# scara_robot.net
KiCad netlist of a schematic drawn in EasyEDA
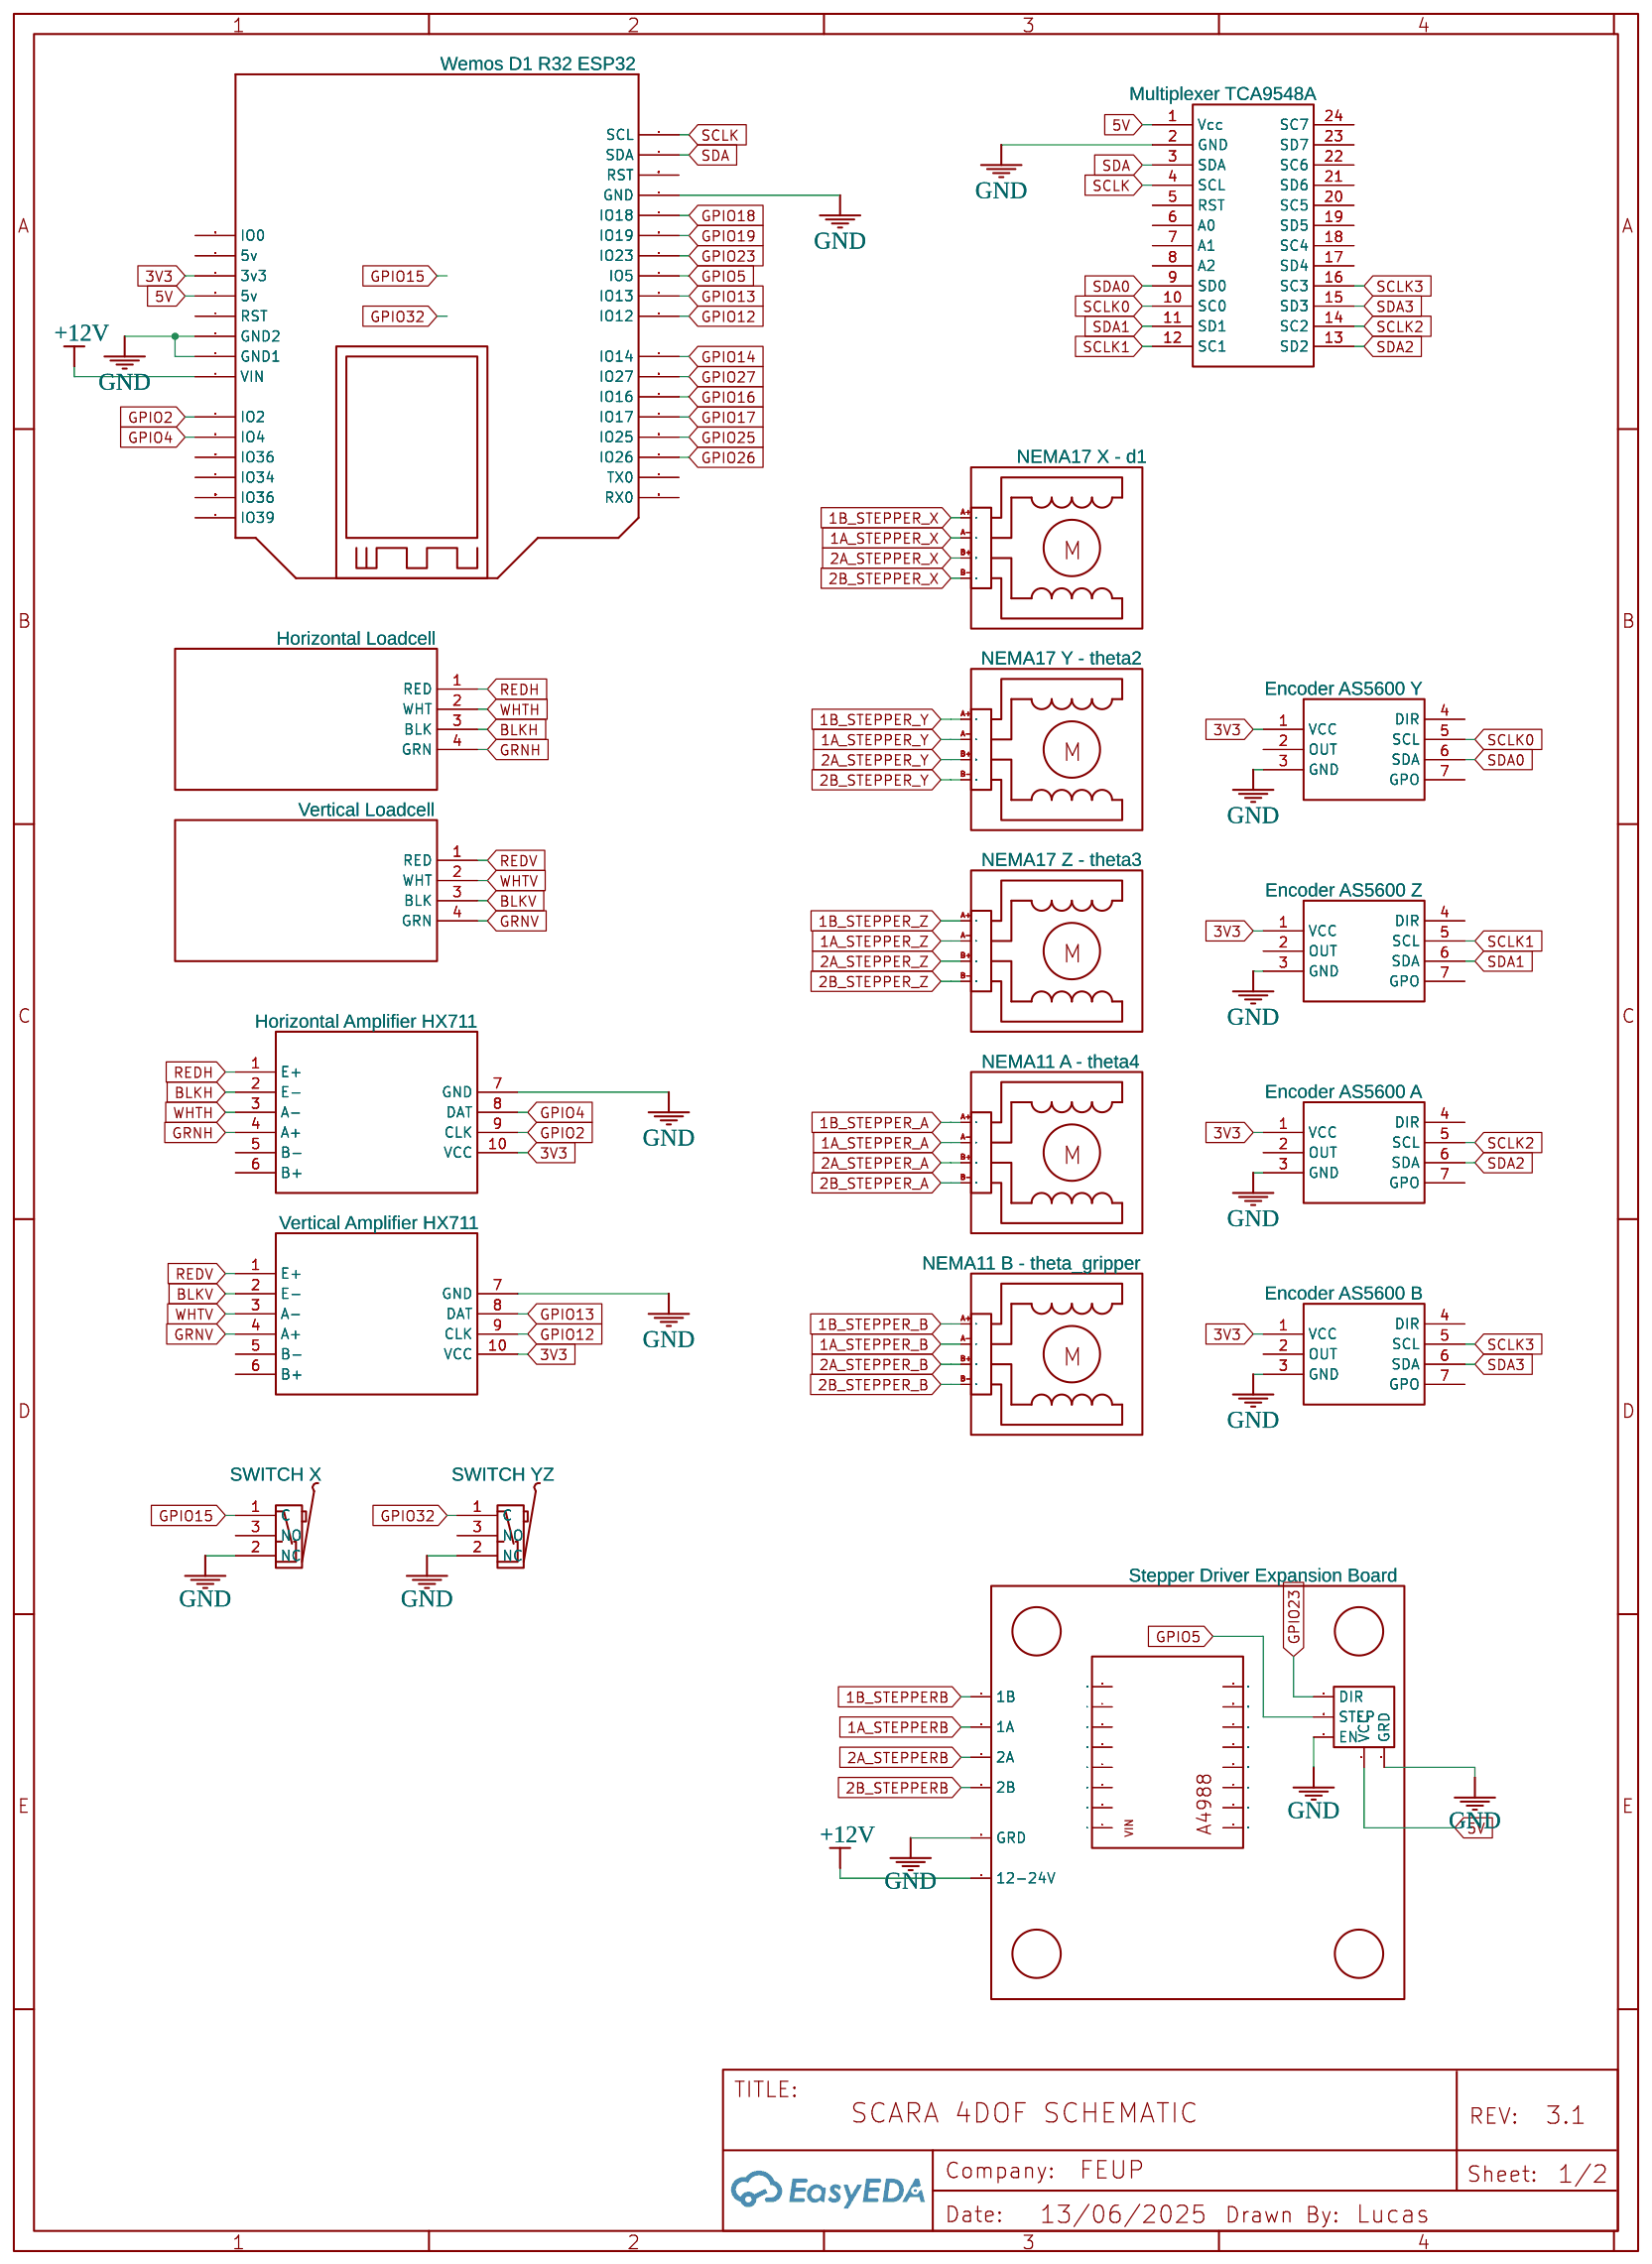
[diagram p0: Sheet_1]
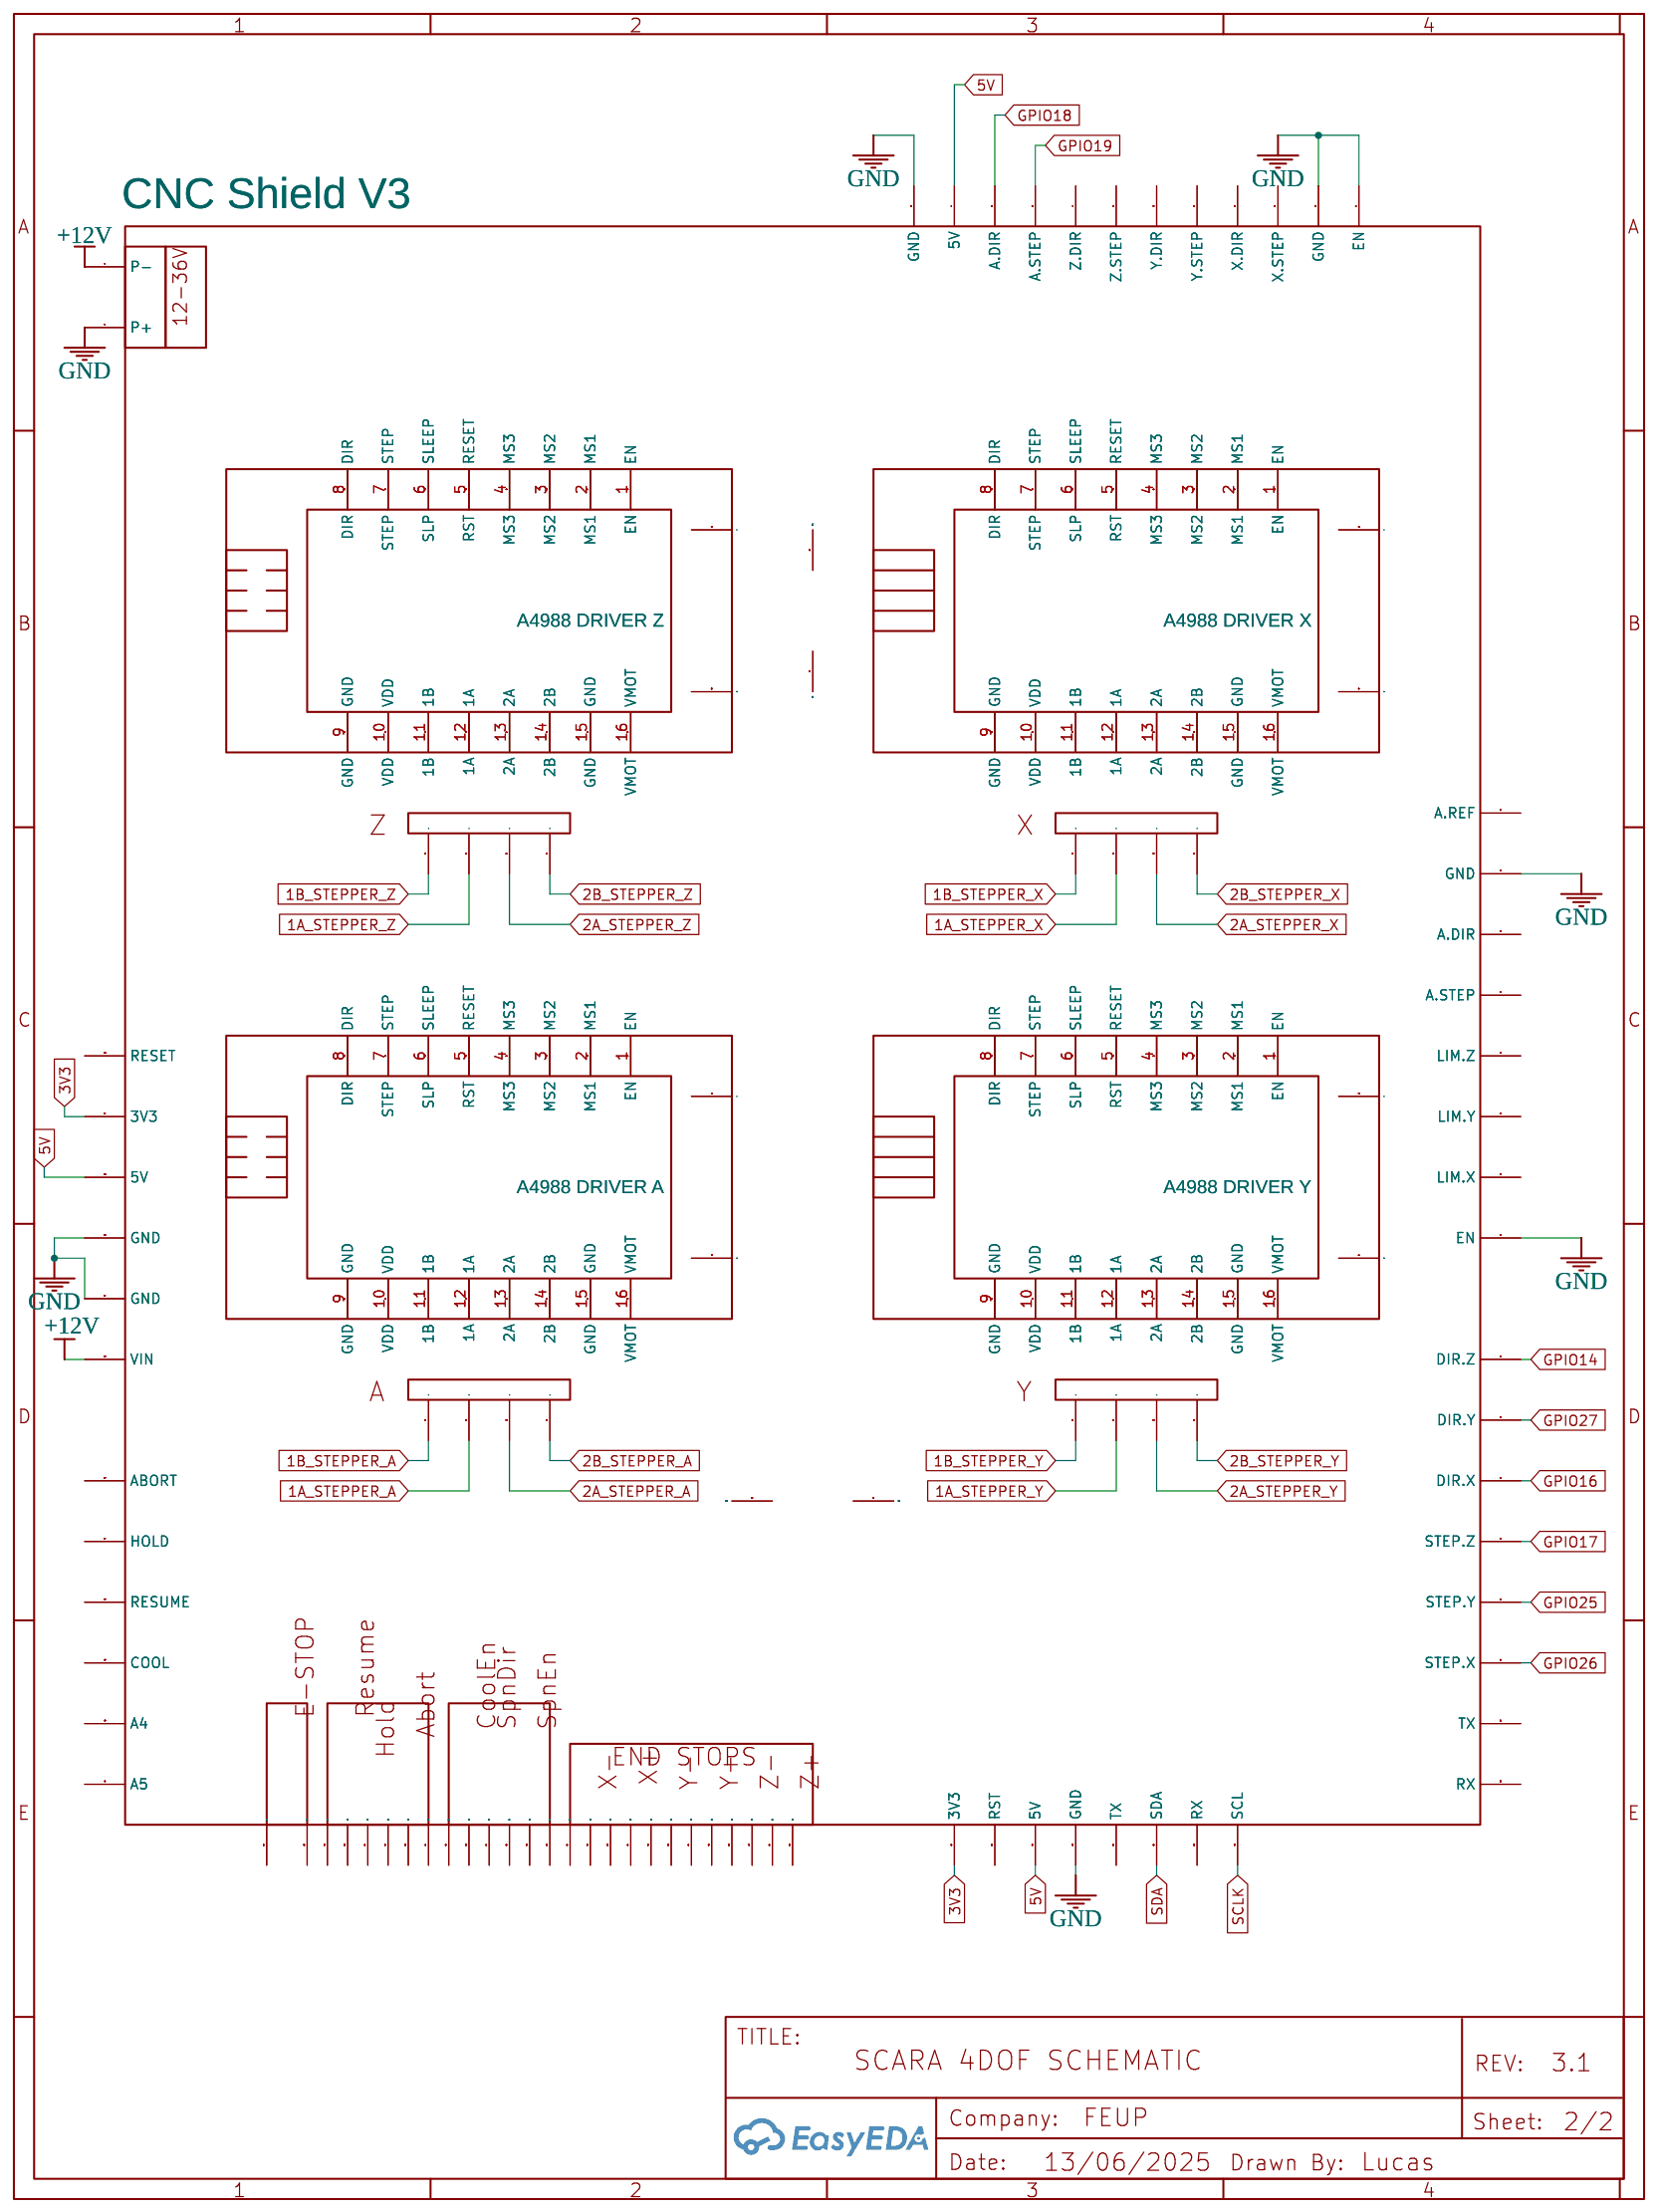
[diagram p1: Sheet_2]

(export (version "E")
  (design (tool "Eeschema 10.0.6"))
  (components
    (comp (ref "M1")
      (value "Multiplexer TCA9548A")
      (fields (field (name "Manufacturer Part") "S.MOD.TCA9548A"))
      (libsource (lib "") (part "multiplexer"))
    )
    (comp (ref "P1")
      (value "NEMA17 Y - theta2")
      (fields
        (field (name "Manufacturer Part") "Header-Male-2.54_1x6")
        (field (name "Manufacturer") "BOOMELE")
      )
      (libsource (lib "") (part "STEPPER MOTOR AM34HD1404-06 COPY"))
    )
    (comp (ref "P2")
      (value "NEMA17 X - d1")
      (fields
        (field (name "Manufacturer Part") "Header-Male-2.54_1x6")
        (field (name "Manufacturer") "BOOMELE")
      )
      (libsource (lib "") (part "STEPPER MOTOR AM34HD1404-06 COPY"))
    )
    (comp (ref "P6")
      (value "NEMA17 Z - theta3")
      (fields
        (field (name "Manufacturer Part") "Header-Male-2.54_1x6")
        (field (name "Manufacturer") "BOOMELE")
      )
      (libsource (lib "") (part "STEPPER MOTOR AM34HD1404-06 COPY"))
    )
    (comp (ref "P7")
      (value "NEMA11 A - theta4")
      (fields
        (field (name "Manufacturer Part") "Header-Male-2.54_1x6")
        (field (name "Manufacturer") "BOOMELE")
      )
      (libsource (lib "") (part "STEPPER MOTOR AM34HD1404-06 COPY"))
    )
    (comp (ref "P8")
      (value "NEMA11 B - theta_gripper")
      (fields
        (field (name "Manufacturer Part") "Header-Male-2.54_1x6")
        (field (name "Manufacturer") "BOOMELE")
      )
      (libsource (lib "") (part "STEPPER MOTOR AM34HD1404-06 COPY"))
    )
    (comp (ref "SW1") (value "SWITCH X") (libsource (lib "") (part "MICROSWITCH")))
    (comp (ref "SW2") (value "SWITCH YZ") (libsource (lib "") (part "MICROSWITCH")))
    (comp (ref "U1") (value "Wemos D1 R32 ESP32") (libsource (lib "") (part "Wemos D1 R32 ESP32")))
    (comp (ref "U5")
      (value "Encoder AS5600 Z")
      (fields (field (name "Manufacturer Part") "Unknown"))
      (libsource (lib "") (part "AS5600"))
    )
    (comp (ref "U6")
      (value "Encoder AS5600 A")
      (fields (field (name "Manufacturer Part") "Unknown"))
      (libsource (lib "") (part "AS5600"))
    )
    (comp (ref "U7")
      (value "Encoder AS5600 B")
      (fields (field (name "Manufacturer Part") "Unknown"))
      (libsource (lib "") (part "AS5600"))
    )
    (comp (ref "U8")
      (value "Encoder AS5600 Y")
      (fields (field (name "Manufacturer Part") "Unknown"))
      (libsource (lib "") (part "AS5600"))
    )
    (comp (ref "U12")
      (value "Horizontal Amplifier HX711")
      (libsource (lib "") (part "HX711 LOAD CELL AMPLIFIER"))
    )
    (comp (ref "U13")
      (value "Vertical Amplifier HX711")
      (libsource (lib "") (part "HX711 LOAD CELL AMPLIFIER"))
    )
    (comp (ref "U14")
      (value "Horizontal Loadcell")
      (fields (field (name "Manufacturer Part") "Loadcell"))
      (libsource (lib "") (part "Loadcell"))
    )
    (comp (ref "U15")
      (value "Vertical Loadcell")
      (fields (field (name "Manufacturer Part") "Loadcell"))
      (libsource (lib "") (part "Loadcell"))
    )
    (comp (ref "U16")
      (value "Stepper Driver Expansion Board")
      (libsource (lib "") (part "42 STEPPER MOTOR DRIVER EXPANSION BOARD"))
    )
    (comp (ref "U2") (value "CNC Shield V3") (libsource (lib "") (part "CNC Shield V3")))
    (comp (ref "U3") (value "A4988 DRIVER A") (libsource (lib "") (part "A4988 CARRIER")))
    (comp (ref "U4") (value "A4988 DRIVER X") (libsource (lib "") (part "A4988 CARRIER")))
    (comp (ref "U9") (value "A4988 DRIVER Z") (libsource (lib "") (part "A4988 CARRIER")))
    (comp (ref "U10") (value "A4988 DRIVER Y") (libsource (lib "") (part "A4988 CARRIER")))
  )
  (nets
    (net (code "1") (name "+12V") (class "Default")
      (node (ref "U1") (pin "VIN") (pinfunction "VIN_VIN") (pintype "passive"))
      (node (ref "U16") (pin "22") (pinfunction "12-24V_22") (pintype "unspecified"))
      (node (ref "U2") (pin "1") (pinfunction "P-_1") (pintype "unspecified"))
      (node (ref "U2") (pin "163") (pinfunction "VIN_163") (pintype "unspecified"))
    )
    (net (code "2") (name "1A_STEPPERB") (class "Default")
      (node (ref "U16") (pin "18") (pinfunction "1A_18") (pintype "unspecified"))
    )
    (net (code "3") (name "1A_STEPPER_A") (class "Default")
      (node (ref "P7") (pin "A-") (pinfunction "A-_A-") (pintype "unspecified"))
      (node (ref "U2") (pin "100") (pinfunction "__100") (pintype "unspecified"))
    )
    (net (code "4") (name "1A_STEPPER_B") (class "Default")
      (node (ref "P8") (pin "A-") (pinfunction "A-_A-") (pintype "unspecified"))
    )
    (net (code "5") (name "1A_STEPPER_X") (class "Default")
      (node (ref "P2") (pin "A-") (pinfunction "A-_A-") (pintype "unspecified"))
      (node (ref "U2") (pin "39") (pinfunction "__39") (pintype "unspecified"))
    )
    (net (code "6") (name "1A_STEPPER_Y") (class "Default")
      (node (ref "P1") (pin "A-") (pinfunction "A-_A-") (pintype "unspecified"))
      (node (ref "U2") (pin "104") (pinfunction "__104") (pintype "unspecified"))
    )
    (net (code "7") (name "1A_STEPPER_Z") (class "Default")
      (node (ref "P6") (pin "A-") (pinfunction "A-_A-") (pintype "unspecified"))
      (node (ref "U2") (pin "96") (pinfunction "__96") (pintype "unspecified"))
    )
    (net (code "8") (name "1B_STEPPERB") (class "Default")
      (node (ref "U16") (pin "17") (pinfunction "1B_17") (pintype "unspecified"))
    )
    (net (code "9") (name "1B_STEPPER_A") (class "Default")
      (node (ref "P7") (pin "A+") (pinfunction "A+_A+") (pintype "unspecified"))
      (node (ref "U2") (pin "99") (pinfunction "__99") (pintype "unspecified"))
    )
    (net (code "10") (name "1B_STEPPER_B") (class "Default")
      (node (ref "P8") (pin "A+") (pinfunction "A+_A+") (pintype "unspecified"))
    )
    (net (code "11") (name "1B_STEPPER_X") (class "Default")
      (node (ref "P2") (pin "A+") (pinfunction "A+_A+") (pintype "unspecified"))
      (node (ref "U2") (pin "38") (pinfunction "__38") (pintype "unspecified"))
    )
    (net (code "12") (name "1B_STEPPER_Y") (class "Default")
      (node (ref "P1") (pin "A+") (pinfunction "A+_A+") (pintype "unspecified"))
      (node (ref "U2") (pin "103") (pinfunction "__103") (pintype "unspecified"))
    )
    (net (code "13") (name "1B_STEPPER_Z") (class "Default")
      (node (ref "P6") (pin "A+") (pinfunction "A+_A+") (pintype "unspecified"))
      (node (ref "U2") (pin "95") (pinfunction "__95") (pintype "unspecified"))
    )
    (net (code "14") (name "2A_STEPPERB") (class "Default")
      (node (ref "U16") (pin "19") (pinfunction "2A_19") (pintype "unspecified"))
    )
    (net (code "15") (name "2A_STEPPER_A") (class "Default")
      (node (ref "P7") (pin "B+") (pinfunction "B+_B+") (pintype "unspecified"))
      (node (ref "U2") (pin "101") (pinfunction "__101") (pintype "unspecified"))
    )
    (net (code "16") (name "2A_STEPPER_B") (class "Default")
      (node (ref "P8") (pin "B+") (pinfunction "B+_B+") (pintype "unspecified"))
    )
    (net (code "17") (name "2A_STEPPER_X") (class "Default")
      (node (ref "P2") (pin "B+") (pinfunction "B+_B+") (pintype "unspecified"))
      (node (ref "U2") (pin "40") (pinfunction "__40") (pintype "unspecified"))
    )
    (net (code "18") (name "2A_STEPPER_Y") (class "Default")
      (node (ref "P1") (pin "B+") (pinfunction "B+_B+") (pintype "unspecified"))
      (node (ref "U2") (pin "105") (pinfunction "__105") (pintype "unspecified"))
    )
    (net (code "19") (name "2A_STEPPER_Z") (class "Default")
      (node (ref "P6") (pin "B+") (pinfunction "B+_B+") (pintype "unspecified"))
      (node (ref "U2") (pin "97") (pinfunction "__97") (pintype "unspecified"))
    )
    (net (code "20") (name "2B_STEPPERB") (class "Default")
      (node (ref "U16") (pin "20") (pinfunction "2B_20") (pintype "unspecified"))
    )
    (net (code "21") (name "2B_STEPPER_A") (class "Default")
      (node (ref "P7") (pin "B-") (pinfunction "B-_B-") (pintype "unspecified"))
      (node (ref "U2") (pin "102") (pinfunction "__102") (pintype "unspecified"))
    )
    (net (code "22") (name "2B_STEPPER_B") (class "Default")
      (node (ref "P8") (pin "B-") (pinfunction "B-_B-") (pintype "unspecified"))
    )
    (net (code "23") (name "2B_STEPPER_X") (class "Default")
      (node (ref "P2") (pin "B-") (pinfunction "B-_B-") (pintype "unspecified"))
      (node (ref "U2") (pin "41") (pinfunction "__41") (pintype "unspecified"))
    )
    (net (code "24") (name "2B_STEPPER_Y") (class "Default")
      (node (ref "P1") (pin "B-") (pinfunction "B-_B-") (pintype "unspecified"))
      (node (ref "U2") (pin "106") (pinfunction "__106") (pintype "unspecified"))
    )
    (net (code "25") (name "2B_STEPPER_Z") (class "Default")
      (node (ref "P6") (pin "B-") (pinfunction "B-_B-") (pintype "unspecified"))
      (node (ref "U2") (pin "98") (pinfunction "__98") (pintype "unspecified"))
    )
    (net (code "26") (name "3V3") (class "Default")
      (node (ref "U1") (pin "3v3") (pinfunction "3v3_3v3") (pintype "unspecified"))
      (node (ref "U12") (pin "10") (pinfunction "VCC_10") (pintype "unspecified"))
      (node (ref "U13") (pin "10") (pinfunction "VCC_10") (pintype "unspecified"))
      (node (ref "U2") (pin "133") (pinfunction "3V3_133") (pintype "unspecified"))
      (node (ref "U2") (pin "167") (pinfunction "3V3_167") (pintype "unspecified"))
      (node (ref "U5") (pin "1") (pinfunction "VCC_1") (pintype "unspecified"))
      (node (ref "U6") (pin "1") (pinfunction "VCC_1") (pintype "unspecified"))
      (node (ref "U7") (pin "1") (pinfunction "VCC_1") (pintype "unspecified"))
      (node (ref "U8") (pin "1") (pinfunction "VCC_1") (pintype "unspecified"))
    )
    (net (code "27") (name "5V") (class "Default")
      (node (ref "M1") (pin "1") (pinfunction "Vcc_1") (pintype "passive"))
      (node (ref "U1") (pin "5v-2") (pinfunction "5v_5v-2") (pintype "passive"))
      (node (ref "U16") (pin "24") (pinfunction "VCC_24") (pintype "unspecified"))
      (node (ref "U2") (pin "135") (pinfunction "5V_135") (pintype "unspecified"))
      (node (ref "U2") (pin "166") (pinfunction "5V_166") (pintype "unspecified"))
      (node (ref "U2") (pin "4") (pinfunction "5V_4") (pintype "unspecified"))
    )
    (net (code "28") (name "BLKH") (class "Default")
      (node (ref "U12") (pin "2") (pinfunction "E-_2") (pintype "unspecified"))
      (node (ref "U14") (pin "3") (pinfunction "BLK_3") (pintype "unspecified"))
    )
    (net (code "29") (name "BLKV") (class "Default")
      (node (ref "U13") (pin "2") (pinfunction "E-_2") (pintype "unspecified"))
      (node (ref "U15") (pin "3") (pinfunction "BLK_3") (pintype "unspecified"))
    )
    (net (code "30") (name "GND") (class "Default")
      (node (ref "M1") (pin "2") (pinfunction "GND_2") (pintype "unspecified"))
      (node (ref "SW1") (pin "2") (pinfunction "NC_2") (pintype "unspecified"))
      (node (ref "SW2") (pin "2") (pinfunction "NC_2") (pintype "unspecified"))
      (node (ref "U1") (pin "GND") (pinfunction "GND_GND") (pintype "unspecified"))
      (node (ref "U1") (pin "GND1") (pinfunction "GND1_GND1") (pintype "passive"))
      (node (ref "U1") (pin "GND2") (pinfunction "GND2_GND2") (pintype "passive"))
      (node (ref "U12") (pin "7") (pinfunction "GND_7") (pintype "unspecified"))
      (node (ref "U13") (pin "7") (pinfunction "GND_7") (pintype "unspecified"))
      (node (ref "U16") (pin "21") (pinfunction "GRD_21") (pintype "unspecified"))
      (node (ref "U16") (pin "23") (pinfunction "GRD_23") (pintype "unspecified"))
      (node (ref "U16") (pin "27") (pinfunction "EN_27") (pintype "unspecified"))
      (node (ref "U2") (pin "13") (pinfunction "GND_13") (pintype "unspecified"))
      (node (ref "U2") (pin "136") (pinfunction "GND_136") (pintype "unspecified"))
      (node (ref "U2") (pin "14") (pinfunction "EN_14") (pintype "unspecified"))
      (node (ref "U2") (pin "142") (pinfunction "GND_142") (pintype "unspecified"))
      (node (ref "U2") (pin "148") (pinfunction "EN_148") (pintype "unspecified"))
      (node (ref "U2") (pin "164") (pinfunction "GND_164") (pintype "unspecified"))
      (node (ref "U2") (pin "165") (pinfunction "GND_165") (pintype "unspecified"))
      (node (ref "U2") (pin "2") (pinfunction "P+_2") (pintype "unspecified"))
      (node (ref "U2") (pin "3") (pinfunction "GND_3") (pintype "unspecified"))
      (node (ref "U5") (pin "3") (pinfunction "GND_3") (pintype "unspecified"))
      (node (ref "U6") (pin "3") (pinfunction "GND_3") (pintype "unspecified"))
      (node (ref "U7") (pin "3") (pinfunction "GND_3") (pintype "unspecified"))
      (node (ref "U8") (pin "3") (pinfunction "GND_3") (pintype "unspecified"))
    )
    (net (code "31") (name "GPIO2") (class "Default")
      (node (ref "U1") (pin "IO2") (pinfunction "IO2_IO2") (pintype "unspecified"))
      (node (ref "U12") (pin "9") (pinfunction "CLK_9") (pintype "unspecified"))
    )
    (net (code "32") (name "GPIO4") (class "Default")
      (node (ref "U1") (pin "IO4") (pinfunction "IO4_IO4") (pintype "unspecified"))
      (node (ref "U12") (pin "8") (pinfunction "DAT_8") (pintype "unspecified"))
    )
    (net (code "33") (name "GPIO5") (class "Default")
      (node (ref "U1") (pin "IO5") (pinfunction "IO5_IO5") (pintype "unspecified"))
      (node (ref "U16") (pin "26") (pinfunction "STEP_26") (pintype "unspecified"))
    )
    (net (code "34") (name "GPIO12") (class "Default")
      (node (ref "U1") (pin "IO12") (pinfunction "IO12_IO12") (pintype "unspecified"))
      (node (ref "U13") (pin "9") (pinfunction "CLK_9") (pintype "unspecified"))
    )
    (net (code "35") (name "GPIO13") (class "Default")
      (node (ref "U1") (pin "IO13") (pinfunction "IO13_IO13") (pintype "unspecified"))
      (node (ref "U13") (pin "8") (pinfunction "DAT_8") (pintype "unspecified"))
    )
    (net (code "36") (name "GPIO14") (class "Default")
      (node (ref "U1") (pin "IO14") (pinfunction "IO14_IO14") (pintype "unspecified"))
      (node (ref "U2") (pin "149") (pinfunction "DIR.Z_149") (pintype "unspecified"))
    )
    (net (code "37") (name "GPIO15") (class "Default")
      (node (ref "SW1") (pin "1") (pinfunction "C_1") (pintype "unspecified"))
    )
    (net (code "38") (name "GPIO16") (class "Default")
      (node (ref "U1") (pin "IO16") (pinfunction "IO16_IO16") (pintype "unspecified"))
      (node (ref "U2") (pin "151") (pinfunction "DIR.X_151") (pintype "unspecified"))
    )
    (net (code "39") (name "GPIO17") (class "Default")
      (node (ref "U1") (pin "IO17") (pinfunction "IO17_IO17") (pintype "unspecified"))
      (node (ref "U2") (pin "152") (pinfunction "STEP.Z_152") (pintype "unspecified"))
    )
    (net (code "40") (name "GPIO18") (class "Default")
      (node (ref "U1") (pin "IO18") (pinfunction "IO18_IO18") (pintype "unspecified"))
      (node (ref "U2") (pin "5") (pinfunction "A.DIR_5") (pintype "unspecified"))
    )
    (net (code "41") (name "GPIO19") (class "Default")
      (node (ref "U1") (pin "IO19") (pinfunction "IO19_IO19") (pintype "unspecified"))
      (node (ref "U2") (pin "6") (pinfunction "A.STEP_6") (pintype "unspecified"))
    )
    (net (code "42") (name "GPIO23") (class "Default")
      (node (ref "U1") (pin "IO23") (pinfunction "IO23_IO23") (pintype "unspecified"))
      (node (ref "U16") (pin "25") (pinfunction "DIR_25") (pintype "unspecified"))
    )
    (net (code "43") (name "GPIO25") (class "Default")
      (node (ref "U1") (pin "IO25") (pinfunction "IO25_IO25") (pintype "unspecified"))
      (node (ref "U2") (pin "153") (pinfunction "STEP.Y_153") (pintype "unspecified"))
    )
    (net (code "44") (name "GPIO26") (class "Default")
      (node (ref "U1") (pin "IO26") (pinfunction "IO26_IO26") (pintype "unspecified"))
      (node (ref "U2") (pin "154") (pinfunction "STEP.X_154") (pintype "unspecified"))
    )
    (net (code "45") (name "GPIO27") (class "Default")
      (node (ref "U1") (pin "!O27") (pinfunction "IO27_!O27") (pintype "unspecified"))
      (node (ref "U2") (pin "150") (pinfunction "DIR.Y_150") (pintype "unspecified"))
    )
    (net (code "46") (name "GPIO32") (class "Default")
      (node (ref "SW2") (pin "1") (pinfunction "C_1") (pintype "unspecified"))
    )
    (net (code "47") (name "GRNH") (class "Default")
      (node (ref "U12") (pin "4") (pinfunction "A+_4") (pintype "unspecified"))
      (node (ref "U14") (pin "4") (pinfunction "GRN_4") (pintype "unspecified"))
    )
    (net (code "48") (name "GRNV") (class "Default")
      (node (ref "U13") (pin "4") (pinfunction "A+_4") (pintype "unspecified"))
      (node (ref "U15") (pin "4") (pinfunction "GRN_4") (pintype "unspecified"))
    )
    (net (code "49") (name "Net-(U2-GND-Pad24)") (class "Default")
      (node (ref "U2") (pin "24") (pinfunction "GND_24") (pintype "unspecified"))
      (node (ref "U4") (pin "15") (pinfunction "GND_15") (pintype "unspecified"))
    )
    (net (code "50") (name "Net-(U2-GND-Pad30)") (class "Default")
      (node (ref "U2") (pin "30") (pinfunction "GND_30") (pintype "unspecified"))
      (node (ref "U4") (pin "9") (pinfunction "GND_9") (pintype "unspecified"))
    )
    (net (code "51") (name "Net-(U2-GND-Pad50)") (class "Default")
      (node (ref "U2") (pin "50") (pinfunction "GND_50") (pintype "unspecified"))
      (node (ref "U9") (pin "15") (pinfunction "GND_15") (pintype "unspecified"))
    )
    (net (code "52") (name "Net-(U2-GND-Pad56)") (class "Default")
      (node (ref "U2") (pin "56") (pinfunction "GND_56") (pintype "unspecified"))
      (node (ref "U9") (pin "9") (pinfunction "GND_9") (pintype "unspecified"))
    )
    (net (code "53") (name "Net-(U2-GND-Pad86)") (class "Default")
      (node (ref "U2") (pin "86") (pinfunction "GND_86") (pintype "unspecified"))
      (node (ref "U3") (pin "15") (pinfunction "GND_15") (pintype "unspecified"))
    )
    (net (code "54") (name "Net-(U2-GND-Pad92)") (class "Default")
      (node (ref "U2") (pin "92") (pinfunction "GND_92") (pintype "unspecified"))
      (node (ref "U3") (pin "9") (pinfunction "GND_9") (pintype "unspecified"))
    )
    (net (code "55") (name "Net-(U3-1A)") (class "Default")
      (node (ref "U2") (pin "89") (pinfunction "1A_89") (pintype "unspecified"))
      (node (ref "U3") (pin "12") (pinfunction "1A_12") (pintype "unspecified"))
    )
    (net (code "56") (name "Net-(U3-1B)") (class "Default")
      (node (ref "U2") (pin "90") (pinfunction "1B_90") (pintype "unspecified"))
      (node (ref "U3") (pin "11") (pinfunction "1B_11") (pintype "unspecified"))
    )
    (net (code "57") (name "Net-(U3-2A)") (class "Default")
      (node (ref "U2") (pin "88") (pinfunction "2A_88") (pintype "unspecified"))
      (node (ref "U3") (pin "13") (pinfunction "2A_13") (pintype "unspecified"))
    )
    (net (code "58") (name "Net-(U3-2B)") (class "Default")
      (node (ref "U2") (pin "87") (pinfunction "2B_87") (pintype "unspecified"))
      (node (ref "U3") (pin "14") (pinfunction "2B_14") (pintype "unspecified"))
    )
    (net (code "59") (name "Net-(U3-DIR)") (class "Default")
      (node (ref "U2") (pin "77") (pinfunction "DIR_77") (pintype "unspecified"))
      (node (ref "U3") (pin "8") (pinfunction "DIR_8") (pintype "unspecified"))
    )
    (net (code "60") (name "Net-(U3-EN)") (class "Default")
      (node (ref "U2") (pin "84") (pinfunction "EN_84") (pintype "unspecified"))
      (node (ref "U3") (pin "1") (pinfunction "EN_1") (pintype "unspecified"))
    )
    (net (code "61") (name "Net-(U3-MS1)") (class "Default")
      (node (ref "U2") (pin "83") (pinfunction "MS1_83") (pintype "unspecified"))
      (node (ref "U3") (pin "2") (pinfunction "MS1_2") (pintype "unspecified"))
    )
    (net (code "62") (name "Net-(U3-MS2)") (class "Default")
      (node (ref "U2") (pin "82") (pinfunction "MS2_82") (pintype "unspecified"))
      (node (ref "U3") (pin "3") (pinfunction "MS2_3") (pintype "unspecified"))
    )
    (net (code "63") (name "Net-(U3-MS3)") (class "Default")
      (node (ref "U2") (pin "81") (pinfunction "MS3_81") (pintype "unspecified"))
      (node (ref "U3") (pin "4") (pinfunction "MS3_4") (pintype "unspecified"))
    )
    (net (code "64") (name "Net-(U3-RST)") (class "Default")
      (node (ref "U2") (pin "80") (pinfunction "RESET_80") (pintype "unspecified"))
      (node (ref "U3") (pin "5") (pinfunction "RST_5") (pintype "unspecified"))
    )
    (net (code "65") (name "Net-(U3-SLP)") (class "Default")
      (node (ref "U2") (pin "79") (pinfunction "SLEEP_79") (pintype "unspecified"))
      (node (ref "U3") (pin "6") (pinfunction "SLP_6") (pintype "unspecified"))
    )
    (net (code "66") (name "Net-(U3-STEP)") (class "Default")
      (node (ref "U2") (pin "78") (pinfunction "STEP_78") (pintype "unspecified"))
      (node (ref "U3") (pin "7") (pinfunction "STEP_7") (pintype "unspecified"))
    )
    (net (code "67") (name "Net-(U3-VDD)") (class "Default")
      (node (ref "U2") (pin "91") (pinfunction "VDD_91") (pintype "unspecified"))
      (node (ref "U3") (pin "10") (pinfunction "VDD_10") (pintype "unspecified"))
    )
    (net (code "68") (name "Net-(U3-VMOT)") (class "Default")
      (node (ref "U2") (pin "85") (pinfunction "VMOT_85") (pintype "unspecified"))
      (node (ref "U3") (pin "16") (pinfunction "VMOT_16") (pintype "unspecified"))
    )
    (net (code "69") (name "Net-(U4-1A)") (class "Default")
      (node (ref "U2") (pin "27") (pinfunction "1A_27") (pintype "unspecified"))
      (node (ref "U4") (pin "12") (pinfunction "1A_12") (pintype "unspecified"))
    )
    (net (code "70") (name "Net-(U4-1B)") (class "Default")
      (node (ref "U2") (pin "28") (pinfunction "1B_28") (pintype "unspecified"))
      (node (ref "U4") (pin "11") (pinfunction "1B_11") (pintype "unspecified"))
    )
    (net (code "71") (name "Net-(U4-2A)") (class "Default")
      (node (ref "U2") (pin "26") (pinfunction "2A_26") (pintype "unspecified"))
      (node (ref "U4") (pin "13") (pinfunction "2A_13") (pintype "unspecified"))
    )
    (net (code "72") (name "Net-(U4-2B)") (class "Default")
      (node (ref "U2") (pin "25") (pinfunction "2B_25") (pintype "unspecified"))
      (node (ref "U4") (pin "14") (pinfunction "2B_14") (pintype "unspecified"))
    )
    (net (code "73") (name "Net-(U4-DIR)") (class "Default")
      (node (ref "U2") (pin "15") (pinfunction "DIR_15") (pintype "unspecified"))
      (node (ref "U4") (pin "8") (pinfunction "DIR_8") (pintype "unspecified"))
    )
    (net (code "74") (name "Net-(U4-EN)") (class "Default")
      (node (ref "U2") (pin "22") (pinfunction "EN_22") (pintype "unspecified"))
      (node (ref "U4") (pin "1") (pinfunction "EN_1") (pintype "unspecified"))
    )
    (net (code "75") (name "Net-(U4-MS1)") (class "Default")
      (node (ref "U2") (pin "21") (pinfunction "MS1_21") (pintype "unspecified"))
      (node (ref "U4") (pin "2") (pinfunction "MS1_2") (pintype "unspecified"))
    )
    (net (code "76") (name "Net-(U4-MS2)") (class "Default")
      (node (ref "U2") (pin "20") (pinfunction "MS2_20") (pintype "unspecified"))
      (node (ref "U4") (pin "3") (pinfunction "MS2_3") (pintype "unspecified"))
    )
    (net (code "77") (name "Net-(U4-MS3)") (class "Default")
      (node (ref "U2") (pin "19") (pinfunction "MS3_19") (pintype "unspecified"))
      (node (ref "U4") (pin "4") (pinfunction "MS3_4") (pintype "unspecified"))
    )
    (net (code "78") (name "Net-(U4-RST)") (class "Default")
      (node (ref "U2") (pin "18") (pinfunction "RESET_18") (pintype "unspecified"))
      (node (ref "U4") (pin "5") (pinfunction "RST_5") (pintype "unspecified"))
    )
    (net (code "79") (name "Net-(U4-SLP)") (class "Default")
      (node (ref "U2") (pin "17") (pinfunction "SLEEP_17") (pintype "unspecified"))
      (node (ref "U4") (pin "6") (pinfunction "SLP_6") (pintype "unspecified"))
    )
    (net (code "80") (name "Net-(U4-STEP)") (class "Default")
      (node (ref "U2") (pin "16") (pinfunction "STEP_16") (pintype "unspecified"))
      (node (ref "U4") (pin "7") (pinfunction "STEP_7") (pintype "unspecified"))
    )
    (net (code "81") (name "Net-(U4-VDD)") (class "Default")
      (node (ref "U2") (pin "29") (pinfunction "VDD_29") (pintype "unspecified"))
      (node (ref "U4") (pin "10") (pinfunction "VDD_10") (pintype "unspecified"))
    )
    (net (code "82") (name "Net-(U4-VMOT)") (class "Default")
      (node (ref "U2") (pin "23") (pinfunction "VMOT_23") (pintype "unspecified"))
      (node (ref "U4") (pin "16") (pinfunction "VMOT_16") (pintype "unspecified"))
    )
    (net (code "83") (name "Net-(U9-1A)") (class "Default")
      (node (ref "U2") (pin "53") (pinfunction "1A_53") (pintype "unspecified"))
      (node (ref "U9") (pin "12") (pinfunction "1A_12") (pintype "unspecified"))
    )
    (net (code "84") (name "Net-(U9-1B)") (class "Default")
      (node (ref "U2") (pin "54") (pinfunction "1B_54") (pintype "unspecified"))
      (node (ref "U9") (pin "11") (pinfunction "1B_11") (pintype "unspecified"))
    )
    (net (code "85") (name "Net-(U9-2A)") (class "Default")
      (node (ref "U2") (pin "52") (pinfunction "2A_52") (pintype "unspecified"))
      (node (ref "U9") (pin "13") (pinfunction "2A_13") (pintype "unspecified"))
    )
    (net (code "86") (name "Net-(U9-2B)") (class "Default")
      (node (ref "U2") (pin "51") (pinfunction "2B_51") (pintype "unspecified"))
      (node (ref "U9") (pin "14") (pinfunction "2B_14") (pintype "unspecified"))
    )
    (net (code "87") (name "Net-(U9-DIR)") (class "Default")
      (node (ref "U2") (pin "42") (pinfunction "DIR_42") (pintype "unspecified"))
      (node (ref "U9") (pin "8") (pinfunction "DIR_8") (pintype "unspecified"))
    )
    (net (code "88") (name "Net-(U9-EN)") (class "Default")
      (node (ref "U2") (pin "48") (pinfunction "EN_48") (pintype "unspecified"))
      (node (ref "U9") (pin "1") (pinfunction "EN_1") (pintype "unspecified"))
    )
    (net (code "89") (name "Net-(U9-MS1)") (class "Default")
      (node (ref "U2") (pin "47") (pinfunction "MS1_47") (pintype "unspecified"))
      (node (ref "U9") (pin "2") (pinfunction "MS1_2") (pintype "unspecified"))
    )
    (net (code "90") (name "Net-(U9-MS2)") (class "Default")
      (node (ref "U2") (pin "169") (pinfunction "MS2_169") (pintype "unspecified"))
      (node (ref "U9") (pin "3") (pinfunction "MS2_3") (pintype "unspecified"))
    )
    (net (code "91") (name "Net-(U9-MS3)") (class "Default")
      (node (ref "U2") (pin "46") (pinfunction "MS3_46") (pintype "unspecified"))
      (node (ref "U9") (pin "4") (pinfunction "MS3_4") (pintype "unspecified"))
    )
    (net (code "92") (name "Net-(U9-RST)") (class "Default")
      (node (ref "U2") (pin "45") (pinfunction "RESET_45") (pintype "unspecified"))
      (node (ref "U9") (pin "5") (pinfunction "RST_5") (pintype "unspecified"))
    )
    (net (code "93") (name "Net-(U9-SLP)") (class "Default")
      (node (ref "U2") (pin "44") (pinfunction "SLEEP_44") (pintype "unspecified"))
      (node (ref "U9") (pin "6") (pinfunction "SLP_6") (pintype "unspecified"))
    )
    (net (code "94") (name "Net-(U9-STEP)") (class "Default")
      (node (ref "U2") (pin "43") (pinfunction "STEP_43") (pintype "unspecified"))
      (node (ref "U9") (pin "7") (pinfunction "STEP_7") (pintype "unspecified"))
    )
    (net (code "95") (name "Net-(U9-VDD)") (class "Default")
      (node (ref "U2") (pin "55") (pinfunction "VDD_55") (pintype "unspecified"))
      (node (ref "U9") (pin "10") (pinfunction "VDD_10") (pintype "unspecified"))
    )
    (net (code "96") (name "Net-(U9-VMOT)") (class "Default")
      (node (ref "U2") (pin "49") (pinfunction "VMOT_49") (pintype "unspecified"))
      (node (ref "U9") (pin "16") (pinfunction "VMOT_16") (pintype "unspecified"))
    )
    (net (code "97") (name "Net-(U10-1A)") (class "Default")
      (node (ref "U10") (pin "12") (pinfunction "1A_12") (pintype "unspecified"))
      (node (ref "U2") (pin "71") (pinfunction "1A_71") (pintype "unspecified"))
    )
    (net (code "98") (name "Net-(U10-1B)") (class "Default")
      (node (ref "U10") (pin "11") (pinfunction "1B_11") (pintype "unspecified"))
      (node (ref "U2") (pin "72") (pinfunction "1B_72") (pintype "unspecified"))
    )
    (net (code "99") (name "Net-(U10-2A)") (class "Default")
      (node (ref "U10") (pin "13") (pinfunction "2A_13") (pintype "unspecified"))
      (node (ref "U2") (pin "70") (pinfunction "2A_70") (pintype "unspecified"))
    )
    (net (code "100") (name "Net-(U10-2B)") (class "Default")
      (node (ref "U10") (pin "14") (pinfunction "2B_14") (pintype "unspecified"))
      (node (ref "U2") (pin "69") (pinfunction "2B_69") (pintype "unspecified"))
    )
    (net (code "101") (name "Net-(U10-DIR)") (class "Default")
      (node (ref "U10") (pin "8") (pinfunction "DIR_8") (pintype "unspecified"))
      (node (ref "U2") (pin "59") (pinfunction "DIR_59") (pintype "unspecified"))
    )
    (net (code "102") (name "Net-(U10-EN)") (class "Default")
      (node (ref "U10") (pin "1") (pinfunction "EN_1") (pintype "unspecified"))
      (node (ref "U2") (pin "66") (pinfunction "EN_66") (pintype "unspecified"))
    )
    (net (code "103") (name "Net-(U10-GND-Pad9)") (class "Default")
      (node (ref "U10") (pin "9") (pinfunction "GND_9") (pintype "unspecified"))
      (node (ref "U2") (pin "74") (pinfunction "GND_74") (pintype "unspecified"))
    )
    (net (code "104") (name "Net-(U10-GND-Pad15)") (class "Default")
      (node (ref "U10") (pin "15") (pinfunction "GND_15") (pintype "unspecified"))
      (node (ref "U2") (pin "68") (pinfunction "GND_68") (pintype "unspecified"))
    )
    (net (code "105") (name "Net-(U10-MS1)") (class "Default")
      (node (ref "U10") (pin "2") (pinfunction "MS1_2") (pintype "unspecified"))
      (node (ref "U2") (pin "65") (pinfunction "MS1_65") (pintype "unspecified"))
    )
    (net (code "106") (name "Net-(U10-MS2)") (class "Default")
      (node (ref "U10") (pin "3") (pinfunction "MS2_3") (pintype "unspecified"))
      (node (ref "U2") (pin "64") (pinfunction "MS2_64") (pintype "unspecified"))
    )
    (net (code "107") (name "Net-(U10-MS3)") (class "Default")
      (node (ref "U10") (pin "4") (pinfunction "MS3_4") (pintype "unspecified"))
      (node (ref "U2") (pin "63") (pinfunction "MS3_63") (pintype "unspecified"))
    )
    (net (code "108") (name "Net-(U10-RST)") (class "Default")
      (node (ref "U10") (pin "5") (pinfunction "RST_5") (pintype "unspecified"))
      (node (ref "U2") (pin "62") (pinfunction "RESET_62") (pintype "unspecified"))
    )
    (net (code "109") (name "Net-(U10-SLP)") (class "Default")
      (node (ref "U10") (pin "6") (pinfunction "SLP_6") (pintype "unspecified"))
      (node (ref "U2") (pin "61") (pinfunction "SLEEP_61") (pintype "unspecified"))
    )
    (net (code "110") (name "Net-(U10-STEP)") (class "Default")
      (node (ref "U10") (pin "7") (pinfunction "STEP_7") (pintype "unspecified"))
      (node (ref "U2") (pin "60") (pinfunction "STEP_60") (pintype "unspecified"))
    )
    (net (code "111") (name "Net-(U10-VDD)") (class "Default")
      (node (ref "U10") (pin "10") (pinfunction "VDD_10") (pintype "unspecified"))
      (node (ref "U2") (pin "73") (pinfunction "VDD_73") (pintype "unspecified"))
    )
    (net (code "112") (name "Net-(U10-VMOT)") (class "Default")
      (node (ref "U10") (pin "16") (pinfunction "VMOT_16") (pintype "unspecified"))
      (node (ref "U2") (pin "67") (pinfunction "VMOT_67") (pintype "unspecified"))
    )
    (net (code "113") (name "REDH") (class "Default")
      (node (ref "U12") (pin "1") (pinfunction "E+_1") (pintype "unspecified"))
      (node (ref "U14") (pin "1") (pinfunction "RED_1") (pintype "unspecified"))
    )
    (net (code "114") (name "REDV") (class "Default")
      (node (ref "U13") (pin "1") (pinfunction "E+_1") (pintype "unspecified"))
      (node (ref "U15") (pin "1") (pinfunction "RED_1") (pintype "unspecified"))
    )
    (net (code "115") (name "SCLK") (class "Default")
      (node (ref "M1") (pin "4") (pinfunction "SCL_4") (pintype "unspecified"))
      (node (ref "U1") (pin "SCl") (pinfunction "SCL_SCl") (pintype "unspecified"))
      (node (ref "U2") (pin "140") (pinfunction "SCL_140") (pintype "unspecified"))
    )
    (net (code "116") (name "SCLK0") (class "Default")
      (node (ref "M1") (pin "10") (pinfunction "SC0_10") (pintype "unspecified"))
      (node (ref "U8") (pin "5") (pinfunction "SCL_5") (pintype "unspecified"))
    )
    (net (code "117") (name "SCLK1") (class "Default")
      (node (ref "M1") (pin "12") (pinfunction "SC1_12") (pintype "unspecified"))
      (node (ref "U5") (pin "5") (pinfunction "SCL_5") (pintype "unspecified"))
    )
    (net (code "118") (name "SCLK2") (class "Default")
      (node (ref "M1") (pin "14") (pinfunction "SC2_14") (pintype "unspecified"))
      (node (ref "U6") (pin "5") (pinfunction "SCL_5") (pintype "unspecified"))
    )
    (net (code "119") (name "SCLK3") (class "Default")
      (node (ref "M1") (pin "16") (pinfunction "SC3_16") (pintype "unspecified"))
      (node (ref "U7") (pin "5") (pinfunction "SCL_5") (pintype "unspecified"))
    )
    (net (code "120") (name "SDA") (class "Default")
      (node (ref "M1") (pin "3") (pinfunction "SDA_3") (pintype "unspecified"))
      (node (ref "U1") (pin "SDA") (pinfunction "SDA_SDA") (pintype "passive"))
      (node (ref "U2") (pin "138") (pinfunction "SDA_138") (pintype "unspecified"))
    )
    (net (code "121") (name "SDA0") (class "Default")
      (node (ref "M1") (pin "9") (pinfunction "SD0_9") (pintype "unspecified"))
      (node (ref "U8") (pin "6") (pinfunction "SDA_6") (pintype "unspecified"))
    )
    (net (code "122") (name "SDA1") (class "Default")
      (node (ref "M1") (pin "11") (pinfunction "SD1_11") (pintype "unspecified"))
      (node (ref "U5") (pin "6") (pinfunction "SDA_6") (pintype "unspecified"))
    )
    (net (code "123") (name "SDA2") (class "Default")
      (node (ref "M1") (pin "13") (pinfunction "SD2_13") (pintype "unspecified"))
      (node (ref "U6") (pin "6") (pinfunction "SDA_6") (pintype "unspecified"))
    )
    (net (code "124") (name "SDA3") (class "Default")
      (node (ref "M1") (pin "15") (pinfunction "SD3_15") (pintype "unspecified"))
      (node (ref "U7") (pin "6") (pinfunction "SDA_6") (pintype "unspecified"))
    )
    (net (code "125") (name "WHTH") (class "Default")
      (node (ref "U12") (pin "3") (pinfunction "A-_3") (pintype "unspecified"))
      (node (ref "U14") (pin "2") (pinfunction "WHT_2") (pintype "unspecified"))
    )
    (net (code "126") (name "WHTV") (class "Default")
      (node (ref "U13") (pin "3") (pinfunction "A-_3") (pintype "unspecified"))
      (node (ref "U15") (pin "2") (pinfunction "WHT_2") (pintype "unspecified"))
    )
    (net (code "127") (name "unconnected-(M1-A0-Pad6)") (class "Default")
      (node (ref "M1") (pin "6") (pinfunction "A0_6") (pintype "unspecified"))
    )
    (net (code "128") (name "unconnected-(M1-A1-Pad7)") (class "Default")
      (node (ref "M1") (pin "7") (pinfunction "A1_7") (pintype "unspecified"))
    )
    (net (code "129") (name "unconnected-(M1-A2-Pad8)") (class "Default")
      (node (ref "M1") (pin "8") (pinfunction "A2_8") (pintype "unspecified"))
    )
    (net (code "130") (name "unconnected-(M1-RST-Pad5)") (class "Default")
      (node (ref "M1") (pin "5") (pinfunction "RST_5") (pintype "unspecified"))
    )
    (net (code "131") (name "unconnected-(M1-SC4-Pad18)") (class "Default")
      (node (ref "M1") (pin "18") (pinfunction "SC4_18") (pintype "unspecified"))
    )
    (net (code "132") (name "unconnected-(M1-SC5-Pad20)") (class "Default")
      (node (ref "M1") (pin "20") (pinfunction "SC5_20") (pintype "unspecified"))
    )
    (net (code "133") (name "unconnected-(M1-SC6-Pad22)") (class "Default")
      (node (ref "M1") (pin "22") (pinfunction "SC6_22") (pintype "unspecified"))
    )
    (net (code "134") (name "unconnected-(M1-SC7-Pad24)") (class "Default")
      (node (ref "M1") (pin "24") (pinfunction "SC7_24") (pintype "unspecified"))
    )
    (net (code "135") (name "unconnected-(M1-SD4-Pad17)") (class "Default")
      (node (ref "M1") (pin "17") (pinfunction "SD4_17") (pintype "unspecified"))
    )
    (net (code "136") (name "unconnected-(M1-SD5-Pad19)") (class "Default")
      (node (ref "M1") (pin "19") (pinfunction "SD5_19") (pintype "unspecified"))
    )
    (net (code "137") (name "unconnected-(M1-SD6-Pad21)") (class "Default")
      (node (ref "M1") (pin "21") (pinfunction "SD6_21") (pintype "unspecified"))
    )
    (net (code "138") (name "unconnected-(M1-SD7-Pad23)") (class "Default")
      (node (ref "M1") (pin "23") (pinfunction "SD7_23") (pintype "unspecified"))
    )
    (net (code "139") (name "unconnected-(SW1-NO-Pad3)") (class "Default")
      (node (ref "SW1") (pin "3") (pinfunction "NO_3") (pintype "unspecified"))
    )
    (net (code "140") (name "unconnected-(SW2-NO-Pad3)") (class "Default")
      (node (ref "SW2") (pin "3") (pinfunction "NO_3") (pintype "unspecified"))
    )
    (net (code "141") (name "unconnected-(U1-5v-Pad5v-1)") (class "Default")
      (node (ref "U1") (pin "5v-1") (pinfunction "5v_5v-1") (pintype "passive"))
    )
    (net (code "142") (name "unconnected-(U1-IO36-PadIO36-1)") (class "Default")
      (node (ref "U1") (pin "IO36-1") (pinfunction "IO36_IO36-1") (pintype "unspecified"))
    )
    (net (code "143") (name "unconnected-(U1-IO36-PadIO36-2)") (class "Default")
      (node (ref "U1") (pin "IO36-2") (pinfunction "IO36_IO36-2") (pintype "unspecified"))
    )
    (net (code "144") (name "unconnected-(U1-PadIO0)") (class "Default")
      (node (ref "U1") (pin "IO0") (pinfunction "IO0_IO0") (pintype "passive"))
    )
    (net (code "145") (name "unconnected-(U1-PadIO34)") (class "Default")
      (node (ref "U1") (pin "IO34") (pinfunction "IO34_IO34") (pintype "unspecified"))
    )
    (net (code "146") (name "unconnected-(U1-PadIO39)") (class "Default")
      (node (ref "U1") (pin "IO39") (pinfunction "IO39_IO39") (pintype "unspecified"))
    )
    (net (code "147") (name "unconnected-(U1-PadRX0)") (class "Default")
      (node (ref "U1") (pin "RX0") (pinfunction "RX0_RX0") (pintype "unspecified"))
    )
    (net (code "148") (name "unconnected-(U1-PadTX0)") (class "Default")
      (node (ref "U1") (pin "TX0") (pinfunction "TX0_TX0") (pintype "unspecified"))
    )
    (net (code "149") (name "unconnected-(U1-RST-Pad-1)") (class "Default")
      (node (ref "U1") (pin "-1") (pinfunction "RST_-1") (pintype "passive"))
    )
    (net (code "150") (name "unconnected-(U1-RST-PadRST-2)") (class "Default")
      (node (ref "U1") (pin "RST-2") (pinfunction "RST_RST-2") (pintype "unspecified"))
    )
    (net (code "151") (name "unconnected-(U2-+-Pad37)") (class "Default")
      (node (ref "U2") (pin "37") (pinfunction "+_37") (pintype "unspecified"))
    )
    (net (code "152") (name "unconnected-(U2-+-Pad58)") (class "Default")
      (node (ref "U2") (pin "58") (pinfunction "+_58") (pintype "unspecified"))
    )
    (net (code "153") (name "unconnected-(U2-+-Pad76)") (class "Default")
      (node (ref "U2") (pin "76") (pinfunction "+_76") (pintype "unspecified"))
    )
    (net (code "154") (name "unconnected-(U2-+-Pad94)") (class "Default")
      (node (ref "U2") (pin "94") (pinfunction "+_94") (pintype "unspecified"))
    )
    (net (code "155") (name "unconnected-(U2-13-Pad107)") (class "Default")
      (node (ref "U2") (pin "107") (pinfunction "13_107") (pintype "unspecified"))
    )
    (net (code "156") (name "unconnected-(U2-14-Pad108)") (class "Default")
      (node (ref "U2") (pin "108") (pinfunction "14_108") (pintype "unspecified"))
    )
    (net (code "157") (name "unconnected-(U2-15-Pad109)") (class "Default")
      (node (ref "U2") (pin "109") (pinfunction "15_109") (pintype "unspecified"))
    )
    (net (code "158") (name "unconnected-(U2-16-Pad110)") (class "Default")
      (node (ref "U2") (pin "110") (pinfunction "16_110") (pintype "unspecified"))
    )
    (net (code "159") (name "unconnected-(U2-17-Pad111)") (class "Default")
      (node (ref "U2") (pin "111") (pinfunction "17_111") (pintype "unspecified"))
    )
    (net (code "160") (name "unconnected-(U2-18-Pad112)") (class "Default")
      (node (ref "U2") (pin "112") (pinfunction "18_112") (pintype "unspecified"))
    )
    (net (code "161") (name "unconnected-(U2-19-Pad113)") (class "Default")
      (node (ref "U2") (pin "113") (pinfunction "19_113") (pintype "unspecified"))
    )
    (net (code "162") (name "unconnected-(U2-20-Pad114)") (class "Default")
      (node (ref "U2") (pin "114") (pinfunction "20_114") (pintype "unspecified"))
    )
    (net (code "163") (name "unconnected-(U2-21-Pad115)") (class "Default")
      (node (ref "U2") (pin "115") (pinfunction "21_115") (pintype "unspecified"))
    )
    (net (code "164") (name "unconnected-(U2-22-Pad116)") (class "Default")
      (node (ref "U2") (pin "116") (pinfunction "22_116") (pintype "unspecified"))
    )
    (net (code "165") (name "unconnected-(U2-23-Pad117)") (class "Default")
      (node (ref "U2") (pin "117") (pinfunction "23_117") (pintype "unspecified"))
    )
    (net (code "166") (name "unconnected-(U2-24-Pad118)") (class "Default")
      (node (ref "U2") (pin "118") (pinfunction "24_118") (pintype "unspecified"))
    )
    (net (code "167") (name "unconnected-(U2-25-Pad119)") (class "Default")
      (node (ref "U2") (pin "119") (pinfunction "25_119") (pintype "unspecified"))
    )
    (net (code "168") (name "unconnected-(U2-26-Pad120)") (class "Default")
      (node (ref "U2") (pin "120") (pinfunction "26_120") (pintype "unspecified"))
    )
    (net (code "169") (name "unconnected-(U2-27-Pad121)") (class "Default")
      (node (ref "U2") (pin "121") (pinfunction "27_121") (pintype "unspecified"))
    )
    (net (code "170") (name "unconnected-(U2-28-Pad122)") (class "Default")
      (node (ref "U2") (pin "122") (pinfunction "28_122") (pintype "unspecified"))
    )
    (net (code "171") (name "unconnected-(U2-29-Pad123)") (class "Default")
      (node (ref "U2") (pin "123") (pinfunction "29_123") (pintype "unspecified"))
    )
    (net (code "172") (name "unconnected-(U2-30-Pad124)") (class "Default")
      (node (ref "U2") (pin "124") (pinfunction "30_124") (pintype "unspecified"))
    )
    (net (code "173") (name "unconnected-(U2-31-Pad125)") (class "Default")
      (node (ref "U2") (pin "125") (pinfunction "31_125") (pintype "unspecified"))
    )
    (net (code "174") (name "unconnected-(U2-32-Pad126)") (class "Default")
      (node (ref "U2") (pin "126") (pinfunction "32_126") (pintype "unspecified"))
    )
    (net (code "175") (name "unconnected-(U2-33-Pad127)") (class "Default")
      (node (ref "U2") (pin "127") (pinfunction "33_127") (pintype "unspecified"))
    )
    (net (code "176") (name "unconnected-(U2-34-Pad128)") (class "Default")
      (node (ref "U2") (pin "128") (pinfunction "34_128") (pintype "unspecified"))
    )
    (net (code "177") (name "unconnected-(U2-35-Pad129)") (class "Default")
      (node (ref "U2") (pin "129") (pinfunction "35_129") (pintype "unspecified"))
    )
    (net (code "178") (name "unconnected-(U2-36-Pad130)") (class "Default")
      (node (ref "U2") (pin "130") (pinfunction "36_130") (pintype "unspecified"))
    )
    (net (code "179") (name "unconnected-(U2-37-Pad131)") (class "Default")
      (node (ref "U2") (pin "131") (pinfunction "37_131") (pintype "unspecified"))
    )
    (net (code "180") (name "unconnected-(U2-38-Pad132)") (class "Default")
      (node (ref "U2") (pin "132") (pinfunction "38_132") (pintype "unspecified"))
    )
    (net (code "181") (name "unconnected-(U2-A.DIR-Pad143)") (class "Default")
      (node (ref "U2") (pin "143") (pinfunction "A.DIR_143") (pintype "unspecified"))
    )
    (net (code "182") (name "unconnected-(U2-A.REF-Pad141)") (class "Default")
      (node (ref "U2") (pin "141") (pinfunction "A.REF_141") (pintype "unspecified"))
    )
    (net (code "183") (name "unconnected-(U2-A.STEP-Pad144)") (class "Default")
      (node (ref "U2") (pin "144") (pinfunction "A.STEP_144") (pintype "unspecified"))
    )
    (net (code "184") (name "unconnected-(U2-A4-Pad158)") (class "Default")
      (node (ref "U2") (pin "158") (pinfunction "A4_158") (pintype "unspecified"))
    )
    (net (code "185") (name "unconnected-(U2-A5-Pad157)") (class "Default")
      (node (ref "U2") (pin "157") (pinfunction "A5_157") (pintype "unspecified"))
    )
    (net (code "186") (name "unconnected-(U2-ABORT-Pad162)") (class "Default")
      (node (ref "U2") (pin "162") (pinfunction "ABORT_162") (pintype "unspecified"))
    )
    (net (code "187") (name "unconnected-(U2-COOL-Pad159)") (class "Default")
      (node (ref "U2") (pin "159") (pinfunction "COOL_159") (pintype "unspecified"))
    )
    (net (code "188") (name "unconnected-(U2-HOLD-Pad161)") (class "Default")
      (node (ref "U2") (pin "161") (pinfunction "HOLD_161") (pintype "unspecified"))
    )
    (net (code "189") (name "unconnected-(U2-LIM.X-Pad147)") (class "Default")
      (node (ref "U2") (pin "147") (pinfunction "LIM.X_147") (pintype "unspecified"))
    )
    (net (code "190") (name "unconnected-(U2-LIM.Y-Pad146)") (class "Default")
      (node (ref "U2") (pin "146") (pinfunction "LIM.Y_146") (pintype "unspecified"))
    )
    (net (code "191") (name "unconnected-(U2-LIM.Z-Pad145)") (class "Default")
      (node (ref "U2") (pin "145") (pinfunction "LIM.Z_145") (pintype "unspecified"))
    )
    (net (code "192") (name "unconnected-(U2-RESET-Pad168)") (class "Default")
      (node (ref "U2") (pin "168") (pinfunction "RESET_168") (pintype "unspecified"))
    )
    (net (code "193") (name "unconnected-(U2-RESET-Pad170)") (class "Default")
      (node (ref "U2") (pin "170") (pinfunction "RESET_170") (pintype "unspecified"))
    )
    (net (code "194") (name "unconnected-(U2-RESET-Pad171)") (class "Default")
      (node (ref "U2") (pin "171") (pinfunction "RESET_171") (pintype "unspecified"))
    )
    (net (code "195") (name "unconnected-(U2-RESET-Pad172)") (class "Default")
      (node (ref "U2") (pin "172") (pinfunction "RESET_172") (pintype "unspecified"))
    )
    (net (code "196") (name "unconnected-(U2-RESET-Pad173)") (class "Default")
      (node (ref "U2") (pin "173") (pinfunction "RESET_173") (pintype "unspecified"))
    )
    (net (code "197") (name "unconnected-(U2-RESUME-Pad160)") (class "Default")
      (node (ref "U2") (pin "160") (pinfunction "RESUME_160") (pintype "unspecified"))
    )
    (net (code "198") (name "unconnected-(U2-RST-Pad134)") (class "Default")
      (node (ref "U2") (pin "134") (pinfunction "RST_134") (pintype "unspecified"))
    )
    (net (code "199") (name "unconnected-(U2-RX-Pad139)") (class "Default")
      (node (ref "U2") (pin "139") (pinfunction "RX_139") (pintype "unspecified"))
    )
    (net (code "200") (name "unconnected-(U2-RX-Pad156)") (class "Default")
      (node (ref "U2") (pin "156") (pinfunction "RX_156") (pintype "unspecified"))
    )
    (net (code "201") (name "unconnected-(U2-TX-Pad137)") (class "Default")
      (node (ref "U2") (pin "137") (pinfunction "TX_137") (pintype "unspecified"))
    )
    (net (code "202") (name "unconnected-(U2-TX-Pad155)") (class "Default")
      (node (ref "U2") (pin "155") (pinfunction "TX_155") (pintype "unspecified"))
    )
    (net (code "203") (name "unconnected-(U2-X.DIR-Pad11)") (class "Default")
      (node (ref "U2") (pin "11") (pinfunction "X.DIR_11") (pintype "unspecified"))
    )
    (net (code "204") (name "unconnected-(U2-X.STEP-Pad12)") (class "Default")
      (node (ref "U2") (pin "12") (pinfunction "X.STEP_12") (pintype "unspecified"))
    )
    (net (code "205") (name "unconnected-(U2-Y.DIR-Pad9)") (class "Default")
      (node (ref "U2") (pin "9") (pinfunction "Y.DIR_9") (pintype "unspecified"))
    )
    (net (code "206") (name "unconnected-(U2-Y.STEP-Pad10)") (class "Default")
      (node (ref "U2") (pin "10") (pinfunction "Y.STEP_10") (pintype "unspecified"))
    )
    (net (code "207") (name "unconnected-(U2-Z.DIR-Pad7)") (class "Default")
      (node (ref "U2") (pin "7") (pinfunction "Z.DIR_7") (pintype "unspecified"))
    )
    (net (code "208") (name "unconnected-(U2-Z.STEP-Pad8)") (class "Default")
      (node (ref "U2") (pin "8") (pinfunction "Z.STEP_8") (pintype "unspecified"))
    )
    (net (code "209") (name "unconnected-(U2-_-Pad36)") (class "Default")
      (node (ref "U2") (pin "36") (pinfunction "__36") (pintype "unspecified"))
    )
    (net (code "210") (name "unconnected-(U2-_-Pad57)") (class "Default")
      (node (ref "U2") (pin "57") (pinfunction "__57") (pintype "unspecified"))
    )
    (net (code "211") (name "unconnected-(U2-_-Pad75)") (class "Default")
      (node (ref "U2") (pin "75") (pinfunction "__75") (pintype "unspecified"))
    )
    (net (code "212") (name "unconnected-(U2-_-Pad93)") (class "Default")
      (node (ref "U2") (pin "93") (pinfunction "__93") (pintype "unspecified"))
    )
    (net (code "213") (name "unconnected-(U5-DIR-Pad4)") (class "Default")
      (node (ref "U5") (pin "4") (pinfunction "DIR_4") (pintype "unspecified"))
    )
    (net (code "214") (name "unconnected-(U5-GPO-Pad7)") (class "Default")
      (node (ref "U5") (pin "7") (pinfunction "GPO_7") (pintype "unspecified"))
    )
    (net (code "215") (name "unconnected-(U5-OUT-Pad2)") (class "Default")
      (node (ref "U5") (pin "2") (pinfunction "OUT_2") (pintype "unspecified"))
    )
    (net (code "216") (name "unconnected-(U6-DIR-Pad4)") (class "Default")
      (node (ref "U6") (pin "4") (pinfunction "DIR_4") (pintype "unspecified"))
    )
    (net (code "217") (name "unconnected-(U6-GPO-Pad7)") (class "Default")
      (node (ref "U6") (pin "7") (pinfunction "GPO_7") (pintype "unspecified"))
    )
    (net (code "218") (name "unconnected-(U6-OUT-Pad2)") (class "Default")
      (node (ref "U6") (pin "2") (pinfunction "OUT_2") (pintype "unspecified"))
    )
    (net (code "219") (name "unconnected-(U7-DIR-Pad4)") (class "Default")
      (node (ref "U7") (pin "4") (pinfunction "DIR_4") (pintype "unspecified"))
    )
    (net (code "220") (name "unconnected-(U7-GPO-Pad7)") (class "Default")
      (node (ref "U7") (pin "7") (pinfunction "GPO_7") (pintype "unspecified"))
    )
    (net (code "221") (name "unconnected-(U7-OUT-Pad2)") (class "Default")
      (node (ref "U7") (pin "2") (pinfunction "OUT_2") (pintype "unspecified"))
    )
    (net (code "222") (name "unconnected-(U8-DIR-Pad4)") (class "Default")
      (node (ref "U8") (pin "4") (pinfunction "DIR_4") (pintype "unspecified"))
    )
    (net (code "223") (name "unconnected-(U8-GPO-Pad7)") (class "Default")
      (node (ref "U8") (pin "7") (pinfunction "GPO_7") (pintype "unspecified"))
    )
    (net (code "224") (name "unconnected-(U8-OUT-Pad2)") (class "Default")
      (node (ref "U8") (pin "2") (pinfunction "OUT_2") (pintype "unspecified"))
    )
    (net (code "225") (name "unconnected-(U12-B+-Pad6)") (class "Default")
      (node (ref "U12") (pin "6") (pinfunction "B+_6") (pintype "unspecified"))
    )
    (net (code "226") (name "unconnected-(U12-B--Pad5)") (class "Default")
      (node (ref "U12") (pin "5") (pinfunction "B-_5") (pintype "unspecified"))
    )
    (net (code "227") (name "unconnected-(U13-B+-Pad6)") (class "Default")
      (node (ref "U13") (pin "6") (pinfunction "B+_6") (pintype "unspecified"))
    )
    (net (code "228") (name "unconnected-(U13-B--Pad5)") (class "Default")
      (node (ref "U13") (pin "5") (pinfunction "B-_5") (pintype "unspecified"))
    )
    (net (code "229") (name "unconnected-(U16-Pad1)") (class "Default")
      (node (ref "U16") (pin "1") (pinfunction "1_1") (pintype "unspecified"))
    )
    (net (code "230") (name "unconnected-(U16-Pad2)") (class "Default")
      (node (ref "U16") (pin "2") (pinfunction "2_2") (pintype "unspecified"))
    )
    (net (code "231") (name "unconnected-(U16-Pad3)") (class "Default")
      (node (ref "U16") (pin "3") (pinfunction "3_3") (pintype "unspecified"))
    )
    (net (code "232") (name "unconnected-(U16-Pad4)") (class "Default")
      (node (ref "U16") (pin "4") (pinfunction "4_4") (pintype "unspecified"))
    )
    (net (code "233") (name "unconnected-(U16-Pad5)") (class "Default")
      (node (ref "U16") (pin "5") (pinfunction "5_5") (pintype "unspecified"))
    )
    (net (code "234") (name "unconnected-(U16-Pad6)") (class "Default")
      (node (ref "U16") (pin "6") (pinfunction "6_6") (pintype "unspecified"))
    )
    (net (code "235") (name "unconnected-(U16-Pad7)") (class "Default")
      (node (ref "U16") (pin "7") (pinfunction "7_7") (pintype "unspecified"))
    )
    (net (code "236") (name "unconnected-(U16-Pad8)") (class "Default")
      (node (ref "U16") (pin "8") (pinfunction "8_8") (pintype "unspecified"))
    )
    (net (code "237") (name "unconnected-(U16-Pad9)") (class "Default")
      (node (ref "U16") (pin "9") (pinfunction "9_9") (pintype "unspecified"))
    )
    (net (code "238") (name "unconnected-(U16-Pad10)") (class "Default")
      (node (ref "U16") (pin "10") (pinfunction "10_10") (pintype "unspecified"))
    )
    (net (code "239") (name "unconnected-(U16-Pad11)") (class "Default")
      (node (ref "U16") (pin "11") (pinfunction "11_11") (pintype "unspecified"))
    )
    (net (code "240") (name "unconnected-(U16-Pad12)") (class "Default")
      (node (ref "U16") (pin "12") (pinfunction "12_12") (pintype "unspecified"))
    )
    (net (code "241") (name "unconnected-(U16-Pad13)") (class "Default")
      (node (ref "U16") (pin "13") (pinfunction "13_13") (pintype "unspecified"))
    )
    (net (code "242") (name "unconnected-(U16-Pad14)") (class "Default")
      (node (ref "U16") (pin "14") (pinfunction "14_14") (pintype "unspecified"))
    )
    (net (code "243") (name "unconnected-(U16-Pad15)") (class "Default")
      (node (ref "U16") (pin "15") (pinfunction "15_15") (pintype "unspecified"))
    )
    (net (code "244") (name "unconnected-(U16-Pad16)") (class "Default")
      (node (ref "U16") (pin "16") (pinfunction "16_16") (pintype "unspecified"))
    )
  )
)
